# SH2_-_CONNECTORS.net
KiCad netlist of a schematic drawn in Altium Designer
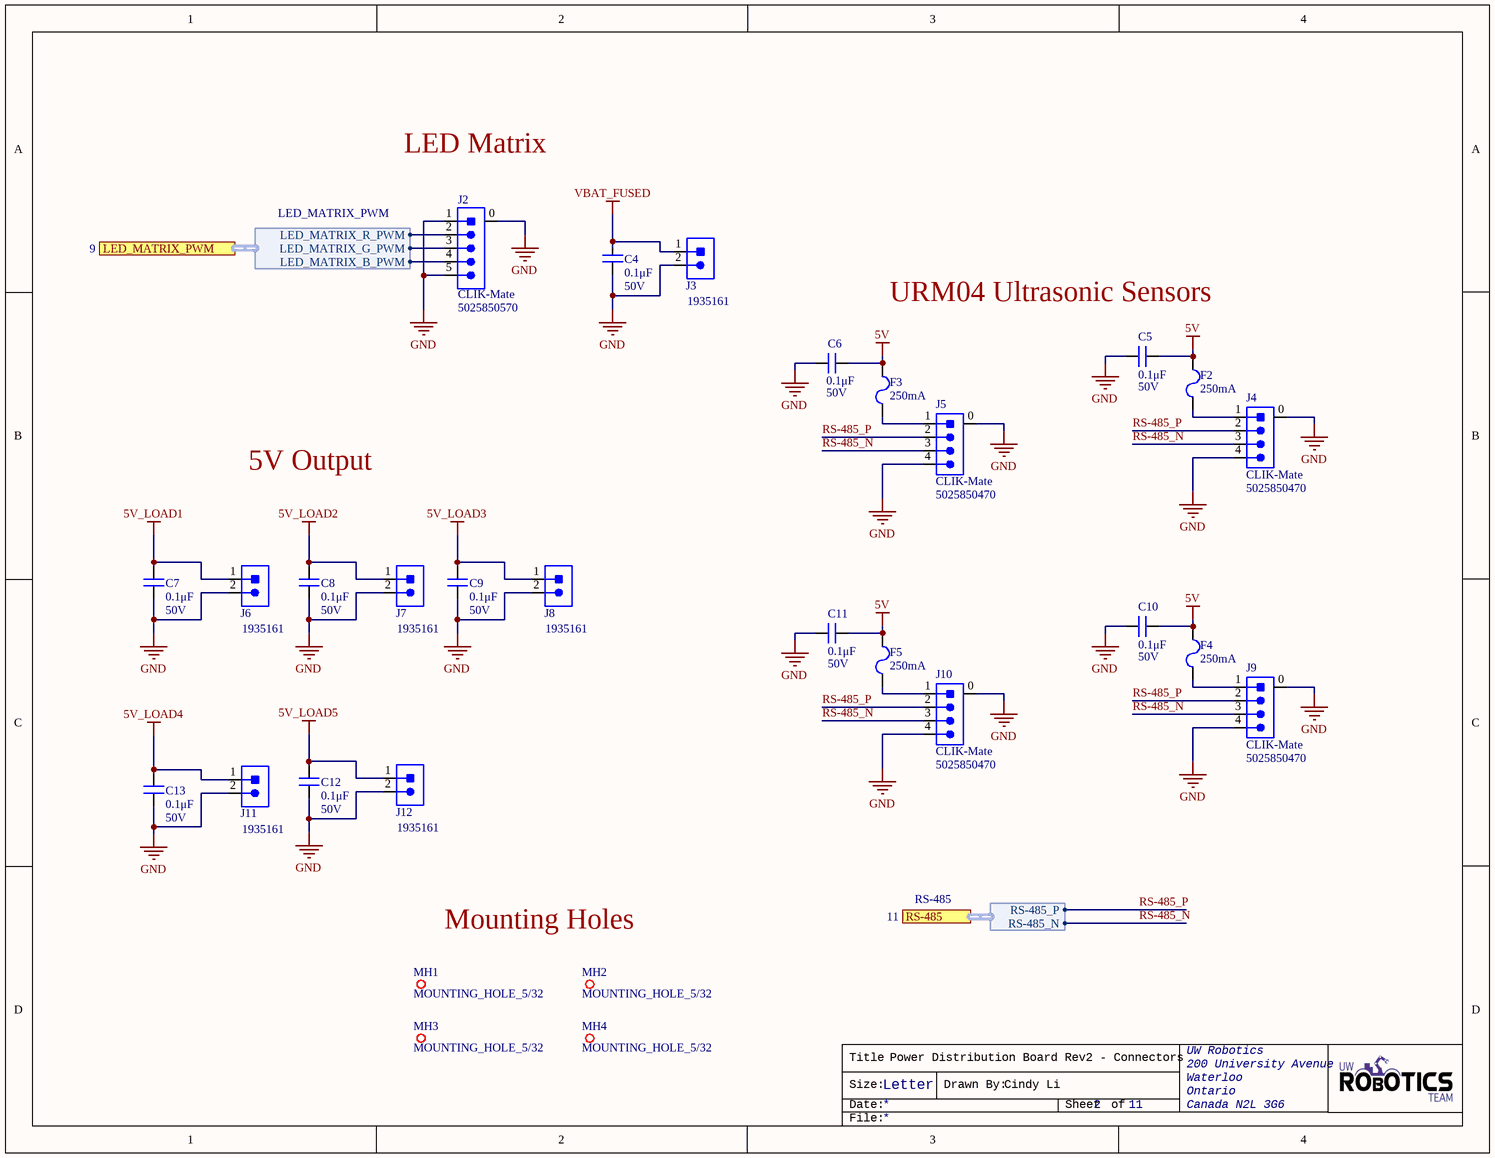
[diagram p0: SH2 - CONNECTORS.SchDoc]

(export (version "E")
  (design (tool "Eeschema 10.0.6"))
  (components
    (comp (ref "C4")
      (value "0.1μF")
      (footprint "CAP2012")
      (description "CAP CER 0.1UF 50V X7R 0805")
      (fields (field (name "TOLERANCE") "10%") (field (name "VOLTAGE RATING") "50V"))
      (libsource (lib "UWRT_Schematic_Library_2020") (part "CAP_0.1uF_50V_0805"))
    )
    (comp (ref "C5")
      (value "0.1μF")
      (footprint "CAP0603")
      (description "CAP CER 0.1UF 50V X7R 0603")
      (fields (field (name "VOLTAGE RATING") "50V") (field (name "Comment") "CAP_0.1uF_50V_0603"))
      (libsource (lib "UWRT_Schematic_Library_2020") (part "CAP_0.1uF_50V_0603"))
    )
    (comp (ref "C6")
      (value "0.1μF")
      (footprint "CAP0603")
      (description "CAP CER 0.1UF 50V X7R 0603")
      (fields (field (name "VOLTAGE RATING") "50V") (field (name "Comment") "CAP_0.1uF_50V_0603"))
      (libsource (lib "UWRT_Schematic_Library_2020") (part "CAP_0.1uF_50V_0603"))
    )
    (comp (ref "C7")
      (value "0.1μF")
      (footprint "CAP2012")
      (description "CAP CER 0.1UF 50V X7R 0805")
      (fields (field (name "TOLERANCE") "10%") (field (name "VOLTAGE RATING") "50V"))
      (libsource (lib "UWRT_Schematic_Library_2020") (part "CAP_0.1uF_50V_0805"))
    )
    (comp (ref "C8")
      (value "0.1μF")
      (footprint "CAP2012")
      (description "CAP CER 0.1UF 50V X7R 0805")
      (fields (field (name "TOLERANCE") "10%") (field (name "VOLTAGE RATING") "50V"))
      (libsource (lib "UWRT_Schematic_Library_2020") (part "CAP_0.1uF_50V_0805"))
    )
    (comp (ref "C9")
      (value "0.1μF")
      (footprint "CAP2012")
      (description "CAP CER 0.1UF 50V X7R 0805")
      (fields (field (name "TOLERANCE") "10%") (field (name "VOLTAGE RATING") "50V"))
      (libsource (lib "UWRT_Schematic_Library_2020") (part "CAP_0.1uF_50V_0805"))
    )
    (comp (ref "C10")
      (value "0.1μF")
      (footprint "CAP0603")
      (description "CAP CER 0.1UF 50V X7R 0603")
      (fields (field (name "VOLTAGE RATING") "50V") (field (name "Comment") "CAP_0.1uF_50V_0603"))
      (libsource (lib "UWRT_Schematic_Library_2020") (part "CAP_0.1uF_50V_0603"))
    )
    (comp (ref "C11")
      (value "0.1μF")
      (footprint "CAP0603")
      (description "CAP CER 0.1UF 50V X7R 0603")
      (fields (field (name "VOLTAGE RATING") "50V") (field (name "Comment") "CAP_0.1uF_50V_0603"))
      (libsource (lib "UWRT_Schematic_Library_2020") (part "CAP_0.1uF_50V_0603"))
    )
    (comp (ref "C12")
      (value "0.1μF")
      (footprint "CAP2012")
      (description "CAP CER 0.1UF 50V X7R 0805")
      (fields (field (name "TOLERANCE") "10%") (field (name "VOLTAGE RATING") "50V"))
      (libsource (lib "UWRT_Schematic_Library_2020") (part "CAP_0.1uF_50V_0805"))
    )
    (comp (ref "C13")
      (value "0.1μF")
      (footprint "CAP2012")
      (description "CAP CER 0.1UF 50V X7R 0805")
      (fields (field (name "TOLERANCE") "10%") (field (name "VOLTAGE RATING") "50V"))
      (libsource (lib "UWRT_Schematic_Library_2020") (part "CAP_0.1uF_50V_0805"))
    )
    (comp (ref "F2")
      (value "FUSE_250mA_0603")
      (footprint "FUSE_0603")
      (description "FUSE SMD 250mA 32V")
      (fields (field (name "CURRENT RATING") "250mA"))
      (libsource (lib "UWRT_Schematic_Library_2020") (part "FUSE_250mA_0603"))
    )
    (comp (ref "F3")
      (value "FUSE_250mA_0603")
      (footprint "FUSE_0603")
      (description "FUSE SMD 250mA 32V")
      (fields (field (name "CURRENT RATING") "250mA"))
      (libsource (lib "UWRT_Schematic_Library_2020") (part "FUSE_250mA_0603"))
    )
    (comp (ref "F4")
      (value "FUSE_250mA_0603")
      (footprint "FUSE_0603")
      (description "FUSE SMD 250mA 32V")
      (fields (field (name "CURRENT RATING") "250mA"))
      (libsource (lib "UWRT_Schematic_Library_2020") (part "FUSE_250mA_0603"))
    )
    (comp (ref "F5")
      (value "FUSE_250mA_0603")
      (footprint "FUSE_0603")
      (description "FUSE SMD 250mA 32V")
      (fields (field (name "CURRENT RATING") "250mA"))
      (libsource (lib "UWRT_Schematic_Library_2020") (part "FUSE_250mA_0603"))
    )
    (comp (ref "J2")
      (value "CON_5M_SM_RA")
      (footprint "MOLEX-5025850570")
      (description "CONN HEADER SMD RIGHT ANGLE 1.5MM PITCH")
      (fields (field (name "FAMILY") "CLIK-Mate") (field (name "MANUFACTURER PART NUMBER 1") "5025850570"))
      (libsource (lib "UWRT_Schematic_Library_2020") (part "CON_5M_SM_RA"))
    )
    (comp (ref "J3")
      (value "1935161")
      (footprint "1935161")
      (description "TERM BLK 2POS SIDE ENTRY 5MM")
      (fields (field (name "VOLTAGE") "300V") (field (name "MANUFACTURER PART NUMBER 1") "1935161"))
      (libsource (lib "UWRT_Schematic_Library_2020") (part "CON_2M_TERM"))
    )
    (comp (ref "J4")
      (value "CON_4M_SM_RA")
      (footprint "MOLEX-5025850470")
      (description "CONN HEADER SMD RIGHT ANGLE 1.5 MM PITCH")
      (fields
        (field (name "MANUFACTURER") "Molex")
        (field (name "FAMILY") "CLIK-Mate")
        (field (name "MANUFACTOR NUMBER") "5025850470")
      )
      (libsource (lib "UWRT_Schematic_Library_2020") (part "CON_4M_SM_RA"))
    )
    (comp (ref "J5")
      (value "CON_4M_SM_RA")
      (footprint "MOLEX-5025850470")
      (description "CONN HEADER SMD RIGHT ANGLE 1.5 MM PITCH")
      (fields
        (field (name "MANUFACTURER") "Molex")
        (field (name "FAMILY") "CLIK-Mate")
        (field (name "MANUFACTOR NUMBER") "5025850470")
      )
      (libsource (lib "UWRT_Schematic_Library_2020") (part "CON_4M_SM_RA"))
    )
    (comp (ref "J6")
      (value "1935161")
      (footprint "1935161")
      (description "TERM BLK 2POS SIDE ENTRY 5MM")
      (fields (field (name "VOLTAGE") "300V") (field (name "MANUFACTURER PART NUMBER 1") "1935161"))
      (libsource (lib "UWRT_Schematic_Library_2020") (part "CON_2M_TERM"))
    )
    (comp (ref "J7")
      (value "1935161")
      (footprint "1935161")
      (description "TERM BLK 2POS SIDE ENTRY 5MM")
      (fields (field (name "VOLTAGE") "300V") (field (name "MANUFACTURER PART NUMBER 1") "1935161"))
      (libsource (lib "UWRT_Schematic_Library_2020") (part "CON_2M_TERM"))
    )
    (comp (ref "J8")
      (value "1935161")
      (footprint "1935161")
      (description "TERM BLK 2POS SIDE ENTRY 5MM")
      (fields (field (name "VOLTAGE") "300V") (field (name "MANUFACTURER PART NUMBER 1") "1935161"))
      (libsource (lib "UWRT_Schematic_Library_2020") (part "CON_2M_TERM"))
    )
    (comp (ref "J9")
      (value "CON_4M_SM_RA")
      (footprint "MOLEX-5025850470")
      (description "CONN HEADER SMD RIGHT ANGLE 1.5 MM PITCH")
      (fields
        (field (name "MANUFACTURER") "Molex")
        (field (name "FAMILY") "CLIK-Mate")
        (field (name "MANUFACTOR NUMBER") "5025850470")
      )
      (libsource (lib "UWRT_Schematic_Library_2020") (part "CON_4M_SM_RA"))
    )
    (comp (ref "J10")
      (value "CON_4M_SM_RA")
      (footprint "MOLEX-5025850470")
      (description "CONN HEADER SMD RIGHT ANGLE 1.5 MM PITCH")
      (fields
        (field (name "MANUFACTURER") "Molex")
        (field (name "FAMILY") "CLIK-Mate")
        (field (name "MANUFACTOR NUMBER") "5025850470")
      )
      (libsource (lib "UWRT_Schematic_Library_2020") (part "CON_4M_SM_RA"))
    )
    (comp (ref "J11")
      (value "1935161")
      (footprint "1935161")
      (description "TERM BLK 2POS SIDE ENTRY 5MM")
      (fields (field (name "VOLTAGE") "300V") (field (name "MANUFACTURER PART NUMBER 1") "1935161"))
      (libsource (lib "UWRT_Schematic_Library_2020") (part "CON_2M_TERM"))
    )
    (comp (ref "J12")
      (value "1935161")
      (footprint "1935161")
      (description "TERM BLK 2POS SIDE ENTRY 5MM")
      (fields (field (name "VOLTAGE") "300V") (field (name "MANUFACTURER PART NUMBER 1") "1935161"))
      (libsource (lib "UWRT_Schematic_Library_2020") (part "CON_2M_TERM"))
    )
    (comp (ref "MH1")
      (value "MOUNTING_HOLE_5/32")
      (footprint "MOUNTING_HOLE_5/38")
      (libsource (lib "UWRT_Schematic_Library_2020") (part "MOUNTING_HOLE_5/32"))
    )
    (comp (ref "MH2")
      (value "MOUNTING_HOLE_5/32")
      (footprint "MOUNTING_HOLE_5/38")
      (libsource (lib "UWRT_Schematic_Library_2020") (part "MOUNTING_HOLE_5/32"))
    )
    (comp (ref "MH3")
      (value "MOUNTING_HOLE_5/32")
      (footprint "MOUNTING_HOLE_5/38")
      (libsource (lib "UWRT_Schematic_Library_2020") (part "MOUNTING_HOLE_5/32"))
    )
    (comp (ref "MH4")
      (value "MOUNTING_HOLE_5/32")
      (footprint "MOUNTING_HOLE_5/38")
      (libsource (lib "UWRT_Schematic_Library_2020") (part "MOUNTING_HOLE_5/32"))
    )
  )
  (nets
    (net (code "3") (name "/LED_MATRIX_B_PWM") (class "Default")
      (node (ref "J2") (pin "4") (pinfunction "4_4") (pintype "passive"))
    )
    (net (code "4") (name "/LED_MATRIX_G_PWM") (class "Default")
      (node (ref "J2") (pin "3") (pinfunction "3_3") (pintype "passive"))
    )
    (net (code "5") (name "/LED_MATRIX_R_PWM") (class "Default")
      (node (ref "J2") (pin "2") (pinfunction "2_2") (pintype "passive"))
    )
    (net (code "6") (name "/RS-485_N") (class "Default")
      (node (ref "J10") (pin "3") (pinfunction "3_3") (pintype "passive"))
      (node (ref "J4") (pin "3") (pinfunction "3_3") (pintype "passive"))
      (node (ref "J5") (pin "3") (pinfunction "3_3") (pintype "passive"))
      (node (ref "J9") (pin "3") (pinfunction "3_3") (pintype "passive"))
    )
    (net (code "7") (name "/RS-485_P") (class "Default")
      (node (ref "J10") (pin "2") (pinfunction "2_2") (pintype "passive"))
      (node (ref "J4") (pin "2") (pinfunction "2_2") (pintype "passive"))
      (node (ref "J5") (pin "2") (pinfunction "2_2") (pintype "passive"))
      (node (ref "J9") (pin "2") (pinfunction "2_2") (pintype "passive"))
    )
    (net (code "10") (name "5V") (class "Default")
      (node (ref "C10") (pin "2") (pinfunction "2_2") (pintype "passive"))
      (node (ref "C11") (pin "2") (pinfunction "2_2") (pintype "passive"))
      (node (ref "C5") (pin "2") (pinfunction "2_2") (pintype "passive"))
      (node (ref "C6") (pin "2") (pinfunction "2_2") (pintype "passive"))
      (node (ref "F2") (pin "2") (pinfunction "2_2") (pintype "passive"))
      (node (ref "F3") (pin "2") (pinfunction "2_2") (pintype "passive"))
      (node (ref "F4") (pin "2") (pinfunction "2_2") (pintype "passive"))
      (node (ref "F5") (pin "2") (pinfunction "2_2") (pintype "passive"))
    )
    (net (code "11") (name "5V_LOAD1") (class "Default")
      (node (ref "C7") (pin "2") (pinfunction "2_2") (pintype "passive"))
      (node (ref "J6") (pin "1") (pinfunction "1_1") (pintype "passive"))
    )
    (net (code "12") (name "5V_LOAD2") (class "Default")
      (node (ref "C8") (pin "2") (pinfunction "2_2") (pintype "passive"))
      (node (ref "J7") (pin "1") (pinfunction "1_1") (pintype "passive"))
    )
    (net (code "13") (name "5V_LOAD3") (class "Default")
      (node (ref "C9") (pin "2") (pinfunction "2_2") (pintype "passive"))
      (node (ref "J8") (pin "1") (pinfunction "1_1") (pintype "passive"))
    )
    (net (code "14") (name "5V_LOAD4") (class "Default")
      (node (ref "C13") (pin "2") (pinfunction "2_2") (pintype "passive"))
      (node (ref "J11") (pin "1") (pinfunction "1_1") (pintype "passive"))
    )
    (net (code "15") (name "5V_LOAD5") (class "Default")
      (node (ref "C12") (pin "2") (pinfunction "2_2") (pintype "passive"))
      (node (ref "J12") (pin "1") (pinfunction "1_1") (pintype "passive"))
    )
    (net (code "16") (name "GND") (class "Default")
      (node (ref "C10") (pin "1") (pinfunction "1_1") (pintype "passive"))
      (node (ref "C11") (pin "1") (pinfunction "1_1") (pintype "passive"))
      (node (ref "C12") (pin "1") (pinfunction "1_1") (pintype "passive"))
      (node (ref "C13") (pin "1") (pinfunction "1_1") (pintype "passive"))
      (node (ref "C4") (pin "1") (pinfunction "1_1") (pintype "passive"))
      (node (ref "C5") (pin "1") (pinfunction "1_1") (pintype "passive"))
      (node (ref "C6") (pin "1") (pinfunction "1_1") (pintype "passive"))
      (node (ref "C7") (pin "1") (pinfunction "1_1") (pintype "passive"))
      (node (ref "C8") (pin "1") (pinfunction "1_1") (pintype "passive"))
      (node (ref "C9") (pin "1") (pinfunction "1_1") (pintype "passive"))
      (node (ref "J10") (pin "0") (pinfunction "0_0") (pintype "passive"))
      (node (ref "J10") (pin "4") (pinfunction "4_4") (pintype "passive"))
      (node (ref "J11") (pin "2") (pinfunction "2_2") (pintype "passive"))
      (node (ref "J12") (pin "2") (pinfunction "2_2") (pintype "passive"))
      (node (ref "J2") (pin "0") (pinfunction "0_0") (pintype "passive"))
      (node (ref "J2") (pin "1") (pinfunction "1_1") (pintype "passive"))
      (node (ref "J2") (pin "5") (pinfunction "5_5") (pintype "passive"))
      (node (ref "J3") (pin "2") (pinfunction "2_2") (pintype "passive"))
      (node (ref "J4") (pin "0") (pinfunction "0_0") (pintype "passive"))
      (node (ref "J4") (pin "4") (pinfunction "4_4") (pintype "passive"))
      (node (ref "J5") (pin "0") (pinfunction "0_0") (pintype "passive"))
      (node (ref "J5") (pin "4") (pinfunction "4_4") (pintype "passive"))
      (node (ref "J6") (pin "2") (pinfunction "2_2") (pintype "passive"))
      (node (ref "J7") (pin "2") (pinfunction "2_2") (pintype "passive"))
      (node (ref "J8") (pin "2") (pinfunction "2_2") (pintype "passive"))
      (node (ref "J9") (pin "0") (pinfunction "0_0") (pintype "passive"))
      (node (ref "J9") (pin "4") (pinfunction "4_4") (pintype "passive"))
    )
    (net (code "17") (name "Net-(F2-Pad1)") (class "Default")
      (node (ref "F2") (pin "1") (pinfunction "1_1") (pintype "passive"))
      (node (ref "J4") (pin "1") (pinfunction "1_1") (pintype "passive"))
    )
    (net (code "18") (name "Net-(F3-Pad1)") (class "Default")
      (node (ref "F3") (pin "1") (pinfunction "1_1") (pintype "passive"))
      (node (ref "J5") (pin "1") (pinfunction "1_1") (pintype "passive"))
    )
    (net (code "19") (name "Net-(F4-Pad1)") (class "Default")
      (node (ref "F4") (pin "1") (pinfunction "1_1") (pintype "passive"))
      (node (ref "J9") (pin "1") (pinfunction "1_1") (pintype "passive"))
    )
    (net (code "20") (name "Net-(F5-Pad1)") (class "Default")
      (node (ref "F5") (pin "1") (pinfunction "1_1") (pintype "passive"))
      (node (ref "J10") (pin "1") (pinfunction "1_1") (pintype "passive"))
    )
    (net (code "21") (name "VBAT_FUSED") (class "Default")
      (node (ref "C4") (pin "2") (pinfunction "2_2") (pintype "passive"))
      (node (ref "J3") (pin "1") (pinfunction "1_1") (pintype "passive"))
    )
  )
)
